# Ports.net
KiCad netlist of a schematic drawn in Altium Designer
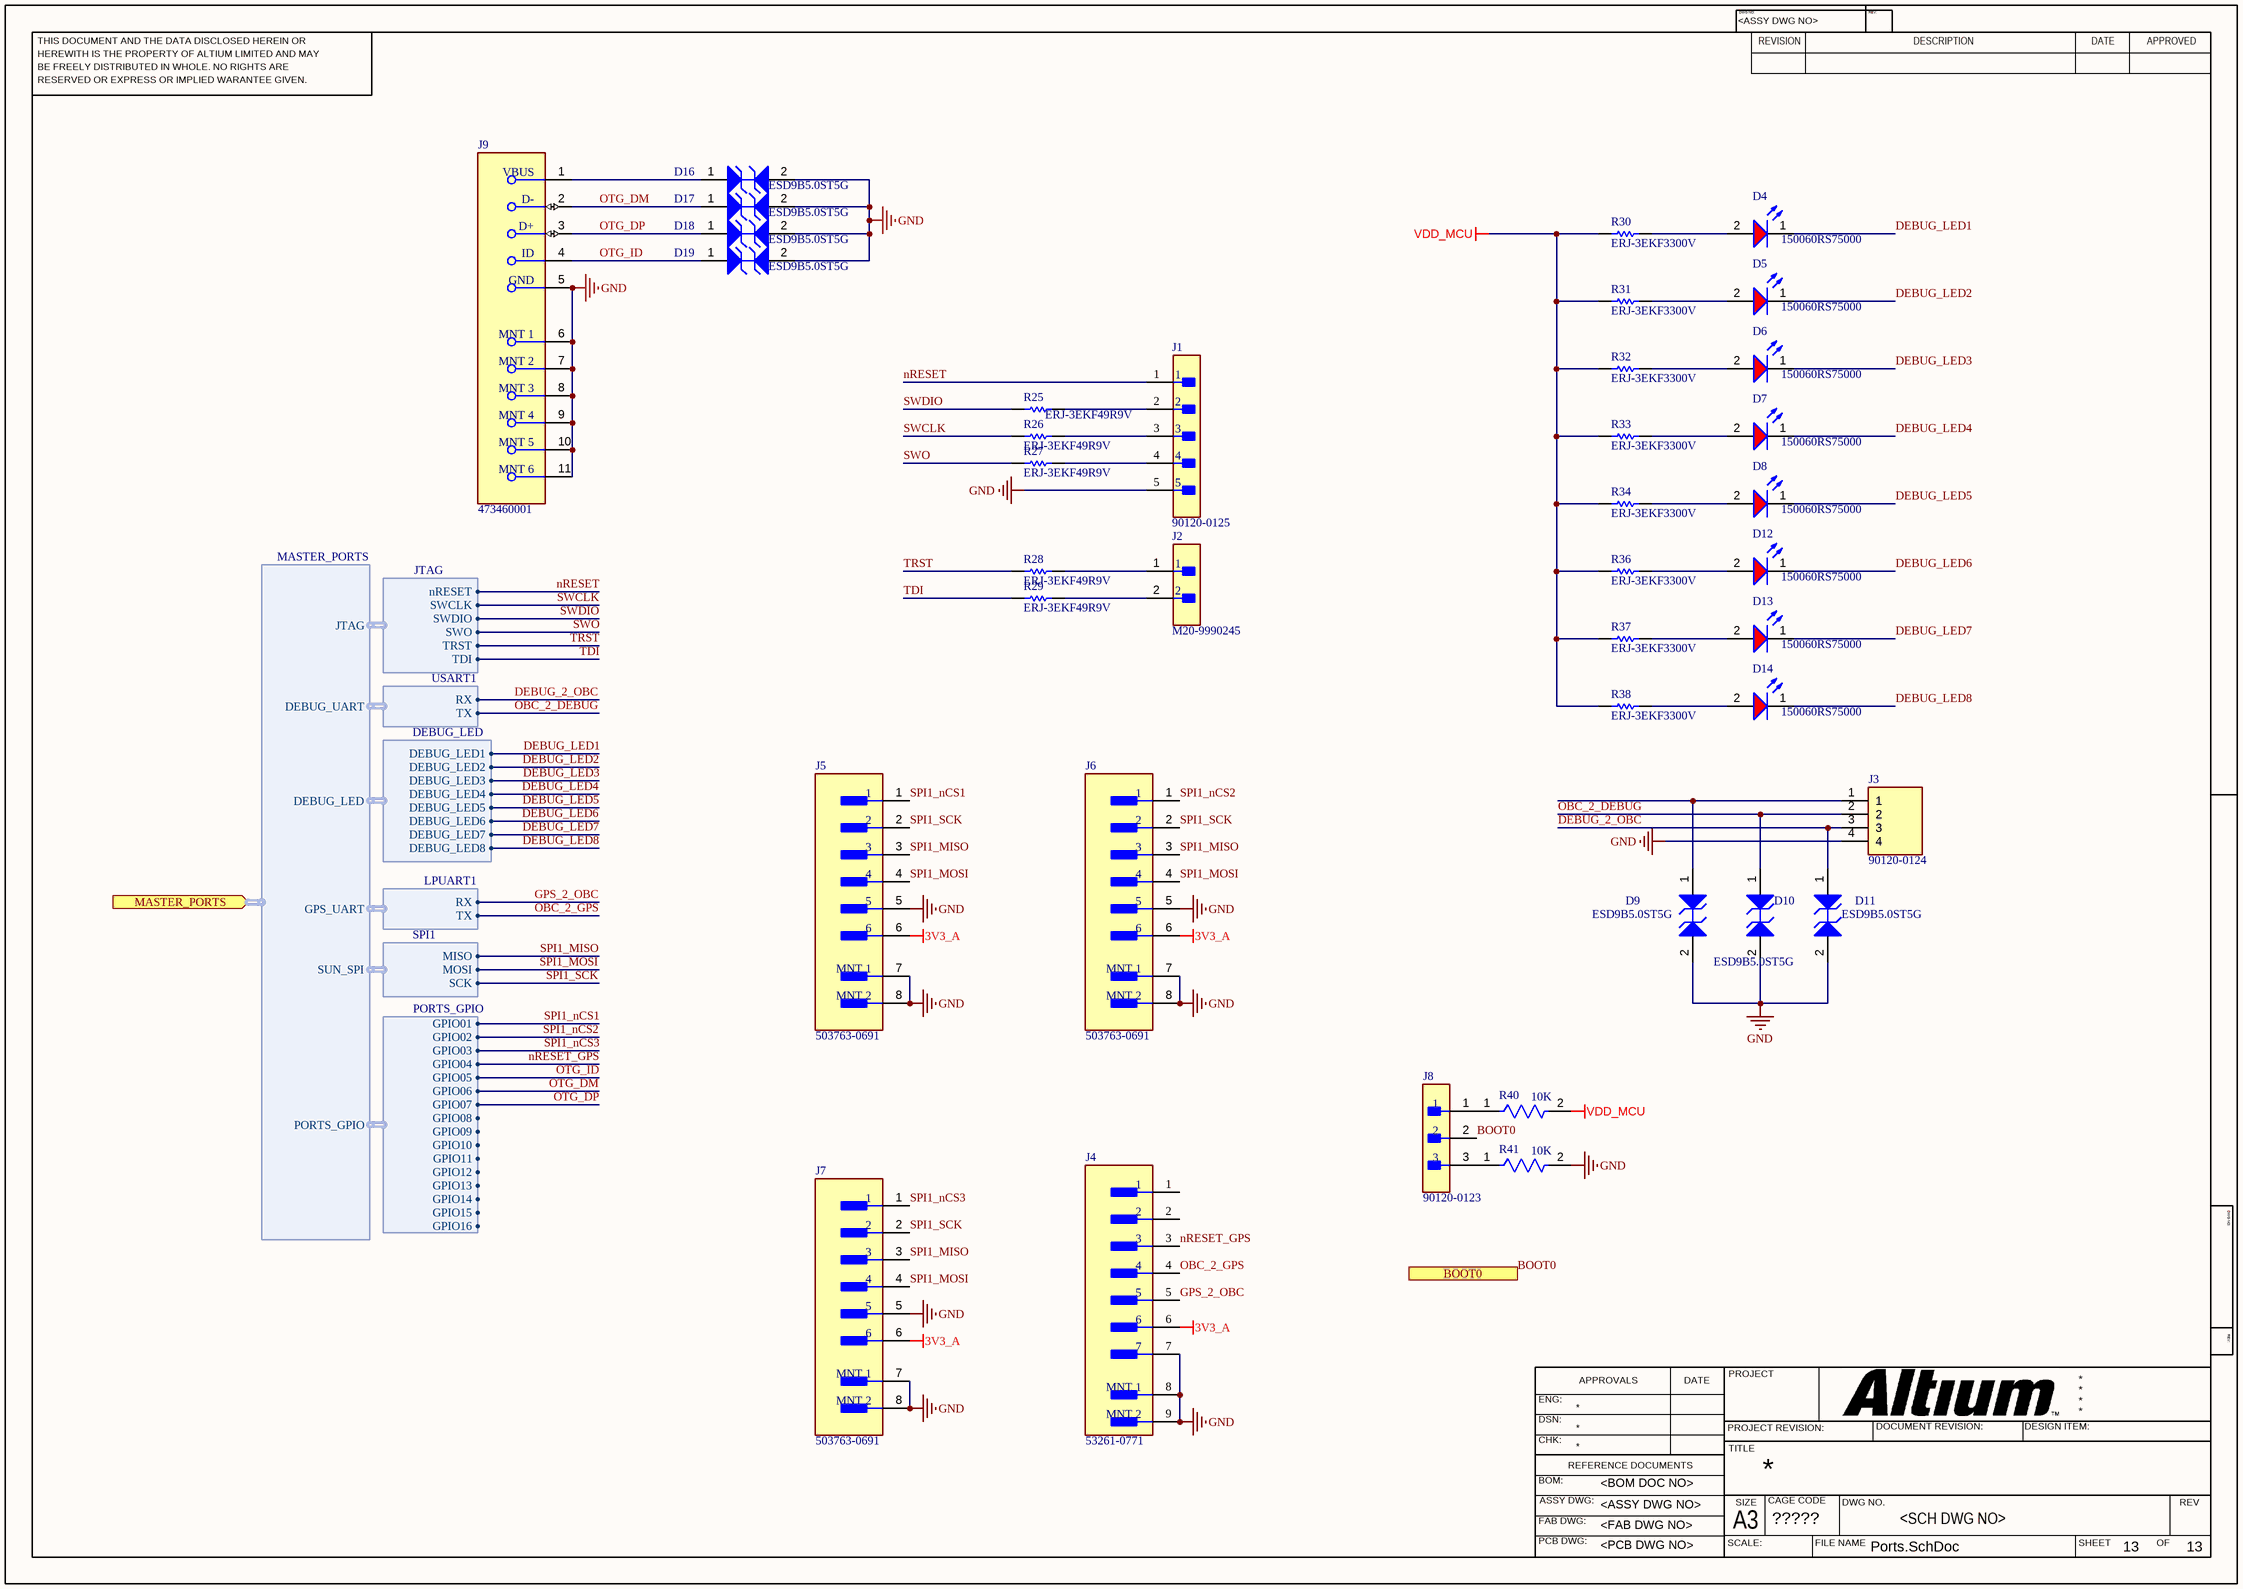
[diagram p0: Ports.SchDoc]

(export (version "E")
  (design (tool "Eeschema 10.0.6"))
  (components
    (comp (ref "D4")
      (value "150060RS75000")
      (footprint "WL-SMCW_0603_150060xx75000")
      (description "LED Low-Power Uni-Color Red 630nm 2V 2-Pin Chip 0603(1608Metric) T/R")
      (libsource (lib "Altium Content Vault") (part "LED_Red_2A-1K"))
    )
    (comp (ref "D5")
      (value "150060RS75000")
      (footprint "WL-SMCW_0603_150060xx75000")
      (description "LED Low-Power Uni-Color Red 630nm 2V 2-Pin Chip 0603(1608Metric) T/R")
      (libsource (lib "Altium Content Vault") (part "LED_Red_2A-1K"))
    )
    (comp (ref "D6")
      (value "150060RS75000")
      (footprint "WL-SMCW_0603_150060xx75000")
      (description "LED Low-Power Uni-Color Red 630nm 2V 2-Pin Chip 0603(1608Metric) T/R")
      (libsource (lib "Altium Content Vault") (part "LED_Red_2A-1K"))
    )
    (comp (ref "D7")
      (value "150060RS75000")
      (footprint "WL-SMCW_0603_150060xx75000")
      (description "LED Low-Power Uni-Color Red 630nm 2V 2-Pin Chip 0603(1608Metric) T/R")
      (libsource (lib "Altium Content Vault") (part "LED_Red_2A-1K"))
    )
    (comp (ref "D8")
      (value "150060RS75000")
      (footprint "WL-SMCW_0603_150060xx75000")
      (description "LED Low-Power Uni-Color Red 630nm 2V 2-Pin Chip 0603(1608Metric) T/R")
      (libsource (lib "Altium Content Vault") (part "LED_Red_2A-1K"))
    )
    (comp (ref "D9")
      (value "ESD9B5.0ST5G")
      (footprint "ONSC-SOD-923-2-514AB-01_V")
      (fields (field (name "MANUFACTURER") "On Semiconductor"))
      (libsource (lib "Altium Content Vault") (part "ONSC-A1A2-2"))
    )
    (comp (ref "D10")
      (value "ESD9B5.0ST5G")
      (footprint "ONSC-SOD-923-2-514AB-01_V")
      (fields (field (name "MANUFACTURER") "On Semiconductor"))
      (libsource (lib "Altium Content Vault") (part "ONSC-A1A2-2"))
    )
    (comp (ref "D11")
      (value "ESD9B5.0ST5G")
      (footprint "ONSC-SOD-923-2-514AB-01_V")
      (fields (field (name "MANUFACTURER") "On Semiconductor"))
      (libsource (lib "Altium Content Vault") (part "ONSC-A1A2-2"))
    )
    (comp (ref "D12")
      (value "150060RS75000")
      (footprint "WL-SMCW_0603_150060xx75000")
      (description "LED Low-Power Uni-Color Red 630nm 2V 2-Pin Chip 0603(1608Metric) T/R")
      (libsource (lib "Altium Content Vault") (part "LED_Red_2A-1K"))
    )
    (comp (ref "D13")
      (value "150060RS75000")
      (footprint "WL-SMCW_0603_150060xx75000")
      (description "LED Low-Power Uni-Color Red 630nm 2V 2-Pin Chip 0603(1608Metric) T/R")
      (libsource (lib "Altium Content Vault") (part "LED_Red_2A-1K"))
    )
    (comp (ref "D14")
      (value "150060RS75000")
      (footprint "WL-SMCW_0603_150060xx75000")
      (description "LED Low-Power Uni-Color Red 630nm 2V 2-Pin Chip 0603(1608Metric) T/R")
      (libsource (lib "Altium Content Vault") (part "LED_Red_2A-1K"))
    )
    (comp (ref "D16")
      (value "ESD9B5.0ST5G")
      (footprint "ONSC-SOD-923-2-514AB-01_V")
      (fields (field (name "MANUFACTURER") "On Semiconductor"))
      (libsource (lib "Altium Content Vault") (part "ONSC-A1A2-2"))
    )
    (comp (ref "D17")
      (value "ESD9B5.0ST5G")
      (footprint "ONSC-SOD-923-2-514AB-01_V")
      (fields (field (name "MANUFACTURER") "On Semiconductor"))
      (libsource (lib "Altium Content Vault") (part "ONSC-A1A2-2"))
    )
    (comp (ref "D18")
      (value "ESD9B5.0ST5G")
      (footprint "ONSC-SOD-923-2-514AB-01_V")
      (fields (field (name "MANUFACTURER") "On Semiconductor"))
      (libsource (lib "Altium Content Vault") (part "ONSC-A1A2-2"))
    )
    (comp (ref "D19")
      (value "ESD9B5.0ST5G")
      (footprint "ONSC-SOD-923-2-514AB-01_V")
      (fields (field (name "MANUFACTURER") "On Semiconductor"))
      (libsource (lib "Altium Content Vault") (part "ONSC-A1A2-2"))
    )
    (comp (ref "J1")
      (value "90120-0125")
      (footprint "FP-90120-0125-MFG")
      (description "90120-0125 2.54mm Pitch C-Grid III Header, Single Row, Vertical, 5 Circuits, Tin (Sn) Plating")
      (libsource (lib "Altium Content Vault") (part "bf93c07fd2649a848d0ec8585582aab"))
    )
    (comp (ref "J2")
      (value "M20-9990245")
      (footprint "FP-M20-9990245-MFG")
      (description "CONN HEADER VERT 2POS 2.54MM")
      (fields (field (name "VOLTAGE") "50V"))
      (libsource (lib "Altium Content Vault") (part "3bc925449376181038e59eaffc5286c"))
    )
    (comp (ref "J3")
      (value "90120-0124")
      (footprint "SamacSys:HDRV4W65P0X254_1X4_1016X254X945P")
      (description "Connector")
      (fields (field (name "MOUSER PART NUMBER") "538-90120-0124"))
      (libsource (lib "*") (part "90120-0124"))
    )
    (comp (ref "J4")
      (value "53261-0771")
      (footprint "FP-53261-0771-MFG")
      (description "CONN HEADER SMD R/A 7POS 1.25MM")
      (libsource (lib "Altium Content Vault") (part "bf8db8d8d9f0c3af2da8de9d3b974a9"))
    )
    (comp (ref "J5")
      (value "503763-0691")
      (footprint "FP-503763-0691-MFG")
      (description "CONN HEADER SMD R/A 6POS 1MM")
      (libsource (lib "Altium Content Vault") (part "ed24c53d9ba001d1a2a686240a95171"))
    )
    (comp (ref "J6")
      (value "503763-0691")
      (footprint "FP-503763-0691-MFG")
      (description "CONN HEADER SMD R/A 6POS 1MM")
      (libsource (lib "Altium Content Vault") (part "ed24c53d9ba001d1a2a686240a95171"))
    )
    (comp (ref "J7")
      (value "503763-0691")
      (footprint "FP-503763-0691-MFG")
      (description "CONN HEADER SMD R/A 6POS 1MM")
      (libsource (lib "Altium Content Vault") (part "ed24c53d9ba001d1a2a686240a95171"))
    )
    (comp (ref "J8")
      (value "90120-0123")
      (footprint "FP-90120-0123-MFG")
      (description "CONN HEADER VERT 3POS 2.54MM")
      (libsource (lib "Altium Content Vault") (part "0d3f023dd272f625e17a2be33dea85f"))
    )
    (comp (ref "J9")
      (value "473460001")
      (footprint "FP-473460001-MFG")
      (description "CONN RCPT USB2.0 MICRO B SMD R/A")
      (fields
        (field (name "OCTOPART") "https://octopart.com/47346-0001-molex-7164928")
        (field (name "MANUFACTURER") "Molex")
      )
      (libsource (lib "Altium Content Vault") (part "53ae1f1d9b557310b43ca686e5bb76a"))
    )
    (comp (ref "R25")
      (value "ERJ-3EKF49R9V")
      (footprint "RESC1608X55X30ML15T15")
      (fields (field (name "MANUFACTURER") "Panasonic"))
      (libsource (lib "Altium Content Vault") (part "RES"))
    )
    (comp (ref "R26")
      (value "ERJ-3EKF49R9V")
      (footprint "RESC1608X55X30ML15T15")
      (fields (field (name "MANUFACTURER") "Panasonic"))
      (libsource (lib "Altium Content Vault") (part "RES"))
    )
    (comp (ref "R27")
      (value "ERJ-3EKF49R9V")
      (footprint "RESC1608X55X30ML15T15")
      (fields (field (name "MANUFACTURER") "Panasonic"))
      (libsource (lib "Altium Content Vault") (part "RES"))
    )
    (comp (ref "R28")
      (value "ERJ-3EKF49R9V")
      (footprint "RESC1608X55X30ML15T15")
      (fields (field (name "MANUFACTURER") "Panasonic"))
      (libsource (lib "Altium Content Vault") (part "RES"))
    )
    (comp (ref "R29")
      (value "ERJ-3EKF49R9V")
      (footprint "RESC1608X55X30ML15T15")
      (fields (field (name "MANUFACTURER") "Panasonic"))
      (libsource (lib "Altium Content Vault") (part "RES"))
    )
    (comp (ref "R30")
      (value "ERJ-3EKF3300V")
      (footprint "RESC1608X55X30LL15T15")
      (description "Chip Resistor, 330 Ohm, +/- 1%, 0.1 W, -55 to 155 degC, 0603 (1608 Metric), RoHS, Tape and Reel")
      (libsource (lib "Altium Content Vault") (part "RES-2"))
    )
    (comp (ref "R31")
      (value "ERJ-3EKF3300V")
      (footprint "RESC1608X55X30LL15T15")
      (description "Chip Resistor, 330 Ohm, +/- 1%, 0.1 W, -55 to 155 degC, 0603 (1608 Metric), RoHS, Tape and Reel")
      (libsource (lib "Altium Content Vault") (part "RES-2"))
    )
    (comp (ref "R32")
      (value "ERJ-3EKF3300V")
      (footprint "RESC1608X55X30LL15T15")
      (description "Chip Resistor, 330 Ohm, +/- 1%, 0.1 W, -55 to 155 degC, 0603 (1608 Metric), RoHS, Tape and Reel")
      (libsource (lib "Altium Content Vault") (part "RES-2"))
    )
    (comp (ref "R33")
      (value "ERJ-3EKF3300V")
      (footprint "RESC1608X55X30LL15T15")
      (description "Chip Resistor, 330 Ohm, +/- 1%, 0.1 W, -55 to 155 degC, 0603 (1608 Metric), RoHS, Tape and Reel")
      (libsource (lib "Altium Content Vault") (part "RES-2"))
    )
    (comp (ref "R34")
      (value "ERJ-3EKF3300V")
      (footprint "RESC1608X55X30LL15T15")
      (description "Chip Resistor, 330 Ohm, +/- 1%, 0.1 W, -55 to 155 degC, 0603 (1608 Metric), RoHS, Tape and Reel")
      (libsource (lib "Altium Content Vault") (part "RES-2"))
    )
    (comp (ref "R36")
      (value "ERJ-3EKF3300V")
      (footprint "RESC1608X55X30LL15T15")
      (description "Chip Resistor, 330 Ohm, +/- 1%, 0.1 W, -55 to 155 degC, 0603 (1608 Metric), RoHS, Tape and Reel")
      (libsource (lib "Altium Content Vault") (part "RES-2"))
    )
    (comp (ref "R37")
      (value "ERJ-3EKF3300V")
      (footprint "RESC1608X55X30LL15T15")
      (description "Chip Resistor, 330 Ohm, +/- 1%, 0.1 W, -55 to 155 degC, 0603 (1608 Metric), RoHS, Tape and Reel")
      (libsource (lib "Altium Content Vault") (part "RES-2"))
    )
    (comp (ref "R38")
      (value "ERJ-3EKF3300V")
      (footprint "RESC1608X55X30LL15T15")
      (description "Chip Resistor, 330 Ohm, +/- 1%, 0.1 W, -55 to 155 degC, 0603 (1608 Metric), RoHS, Tape and Reel")
      (libsource (lib "Altium Content Vault") (part "RES-2"))
    )
    (comp (ref "R40")
      (value "10K")
      (footprint "FP-RK73B1J-MFG")
      (description "RES 10K OHM 5% 1/10W 0603")
      (fields (field (name "TOLERANCE") "5%"))
      (libsource (lib "Altium Content Vault") (part "1029c3af85768c4190bb7ad29bc67b5"))
    )
    (comp (ref "R41")
      (value "10K")
      (footprint "FP-RK73B1J-MFG")
      (description "RES 10K OHM 5% 1/10W 0603")
      (fields (field (name "TOLERANCE") "5%"))
      (libsource (lib "Altium Content Vault") (part "1029c3af85768c4190bb7ad29bc67b5"))
    )
  )
  (nets
    (net (code "8") (name "/BOOT0") (class "Default")
      (node (ref "J8") (pin "2") (pinfunction "2_2") (pintype "passive"))
    )
    (net (code "9") (name "/DEBUG_2_OBC") (class "Default")
      (node (ref "D11") (pin "1") (pinfunction "A1_1") (pintype "passive"))
      (node (ref "J3") (pin "3") (pinfunction "3_3") (pintype "passive"))
    )
    (net (code "10") (name "/DEBUG_LED1") (class "Default")
      (node (ref "D4") (pin "1") (pinfunction "K_1") (pintype "passive"))
    )
    (net (code "11") (name "/DEBUG_LED2") (class "Default")
      (node (ref "D5") (pin "1") (pinfunction "K_1") (pintype "passive"))
    )
    (net (code "12") (name "/DEBUG_LED3") (class "Default")
      (node (ref "D6") (pin "1") (pinfunction "K_1") (pintype "passive"))
    )
    (net (code "13") (name "/DEBUG_LED4") (class "Default")
      (node (ref "D7") (pin "1") (pinfunction "K_1") (pintype "passive"))
    )
    (net (code "14") (name "/DEBUG_LED5") (class "Default")
      (node (ref "D8") (pin "1") (pinfunction "K_1") (pintype "passive"))
    )
    (net (code "15") (name "/DEBUG_LED6") (class "Default")
      (node (ref "D12") (pin "1") (pinfunction "K_1") (pintype "passive"))
    )
    (net (code "16") (name "/DEBUG_LED7") (class "Default")
      (node (ref "D13") (pin "1") (pinfunction "K_1") (pintype "passive"))
    )
    (net (code "17") (name "/DEBUG_LED8") (class "Default")
      (node (ref "D14") (pin "1") (pinfunction "K_1") (pintype "passive"))
    )
    (net (code "18") (name "/GPS_2_OBC") (class "Default")
      (node (ref "J4") (pin "5") (pinfunction "5_5") (pintype "passive"))
    )
    (net (code "20") (name "/OBC_2_DEBUG") (class "Default")
      (node (ref "D10") (pin "1") (pinfunction "A1_1") (pintype "passive"))
      (node (ref "J3") (pin "2") (pinfunction "2_2") (pintype "passive"))
    )
    (net (code "21") (name "/OBC_2_GPS") (class "Default")
      (node (ref "J4") (pin "4") (pinfunction "4_4") (pintype "passive"))
    )
    (net (code "22") (name "/OTG_DM") (class "Default")
      (node (ref "D17") (pin "1") (pinfunction "A1_1") (pintype "passive"))
      (node (ref "J9") (pin "2") (pinfunction "D-_2") (pintype "bidirectional"))
    )
    (net (code "23") (name "/OTG_DP") (class "Default")
      (node (ref "D18") (pin "1") (pinfunction "A1_1") (pintype "passive"))
      (node (ref "J9") (pin "3") (pinfunction "D+_3") (pintype "bidirectional"))
    )
    (net (code "24") (name "/OTG_ID") (class "Default")
      (node (ref "D19") (pin "1") (pinfunction "A1_1") (pintype "passive"))
      (node (ref "J9") (pin "4") (pinfunction "ID_4") (pintype "passive"))
    )
    (net (code "25") (name "/SPI1_MISO") (class "Default")
      (node (ref "J5") (pin "3") (pinfunction "3_3") (pintype "passive"))
      (node (ref "J6") (pin "3") (pinfunction "3_3") (pintype "passive"))
      (node (ref "J7") (pin "3") (pinfunction "3_3") (pintype "passive"))
    )
    (net (code "26") (name "/SPI1_MOSI") (class "Default")
      (node (ref "J5") (pin "4") (pinfunction "4_4") (pintype "passive"))
      (node (ref "J6") (pin "4") (pinfunction "4_4") (pintype "passive"))
      (node (ref "J7") (pin "4") (pinfunction "4_4") (pintype "passive"))
    )
    (net (code "27") (name "/SPI1_SCK") (class "Default")
      (node (ref "J5") (pin "2") (pinfunction "2_2") (pintype "passive"))
      (node (ref "J6") (pin "2") (pinfunction "2_2") (pintype "passive"))
      (node (ref "J7") (pin "2") (pinfunction "2_2") (pintype "passive"))
    )
    (net (code "28") (name "/SPI1_nCS1") (class "Default")
      (node (ref "J5") (pin "1") (pinfunction "1_1") (pintype "passive"))
    )
    (net (code "29") (name "/SPI1_nCS2") (class "Default")
      (node (ref "J6") (pin "1") (pinfunction "1_1") (pintype "passive"))
    )
    (net (code "30") (name "/SPI1_nCS3") (class "Default")
      (node (ref "J7") (pin "1") (pinfunction "1_1") (pintype "passive"))
    )
    (net (code "31") (name "/SWCLK") (class "Default")
      (node (ref "R26") (pin "1") (pinfunction "1_1") (pintype "passive"))
    )
    (net (code "32") (name "/SWDIO") (class "Default")
      (node (ref "R25") (pin "1") (pinfunction "1_1") (pintype "passive"))
    )
    (net (code "33") (name "/SWO") (class "Default")
      (node (ref "R27") (pin "1") (pinfunction "1_1") (pintype "passive"))
    )
    (net (code "34") (name "/TDI") (class "Default")
      (node (ref "R29") (pin "1") (pinfunction "1_1") (pintype "passive"))
    )
    (net (code "35") (name "/TRST") (class "Default")
      (node (ref "R28") (pin "1") (pinfunction "1_1") (pintype "passive"))
    )
    (net (code "36") (name "/nRESET") (class "Default")
      (node (ref "J1") (pin "1") (pinfunction "1_1") (pintype "passive"))
    )
    (net (code "37") (name "/nRESET_GPS") (class "Default")
      (node (ref "J4") (pin "3") (pinfunction "3_3") (pintype "passive"))
    )
    (net (code "44") (name "3V3_A") (class "Default")
      (node (ref "J4") (pin "6") (pinfunction "6_6") (pintype "passive"))
      (node (ref "J5") (pin "6") (pinfunction "6_6") (pintype "passive"))
      (node (ref "J6") (pin "6") (pinfunction "6_6") (pintype "passive"))
      (node (ref "J7") (pin "6") (pinfunction "6_6") (pintype "passive"))
    )
    (net (code "45") (name "GND") (class "Default")
      (node (ref "D10") (pin "2") (pinfunction "A2_2") (pintype "passive"))
      (node (ref "D11") (pin "2") (pinfunction "A2_2") (pintype "passive"))
      (node (ref "D16") (pin "2") (pinfunction "A2_2") (pintype "passive"))
      (node (ref "D17") (pin "2") (pinfunction "A2_2") (pintype "passive"))
      (node (ref "D18") (pin "2") (pinfunction "A2_2") (pintype "passive"))
      (node (ref "D19") (pin "2") (pinfunction "A2_2") (pintype "passive"))
      (node (ref "D9") (pin "2") (pinfunction "A2_2") (pintype "passive"))
      (node (ref "J1") (pin "5") (pinfunction "5_5") (pintype "passive"))
      (node (ref "J3") (pin "4") (pinfunction "4_4") (pintype "passive"))
      (node (ref "J4") (pin "7") (pinfunction "7_7") (pintype "passive"))
      (node (ref "J4") (pin "8") (pinfunction "MNT_1_8") (pintype "passive"))
      (node (ref "J4") (pin "9") (pinfunction "MNT_2_9") (pintype "passive"))
      (node (ref "J5") (pin "5") (pinfunction "5_5") (pintype "passive"))
      (node (ref "J5") (pin "7") (pinfunction "MNT_1_7") (pintype "passive"))
      (node (ref "J5") (pin "8") (pinfunction "MNT_2_8") (pintype "passive"))
      (node (ref "J6") (pin "5") (pinfunction "5_5") (pintype "passive"))
      (node (ref "J6") (pin "7") (pinfunction "MNT_1_7") (pintype "passive"))
      (node (ref "J6") (pin "8") (pinfunction "MNT_2_8") (pintype "passive"))
      (node (ref "J7") (pin "5") (pinfunction "5_5") (pintype "passive"))
      (node (ref "J7") (pin "7") (pinfunction "MNT_1_7") (pintype "passive"))
      (node (ref "J7") (pin "8") (pinfunction "MNT_2_8") (pintype "passive"))
      (node (ref "J9") (pin "10") (pinfunction "MNT_5_10") (pintype "passive"))
      (node (ref "J9") (pin "11") (pinfunction "MNT_6_11") (pintype "passive"))
      (node (ref "J9") (pin "5") (pinfunction "GND_5") (pintype "power_in"))
      (node (ref "J9") (pin "6") (pinfunction "MNT_1_6") (pintype "passive"))
      (node (ref "J9") (pin "7") (pinfunction "MNT_2_7") (pintype "passive"))
      (node (ref "J9") (pin "8") (pinfunction "MNT_3_8") (pintype "passive"))
      (node (ref "J9") (pin "9") (pinfunction "MNT_4_9") (pintype "passive"))
      (node (ref "R41") (pin "2") (pinfunction "2_2") (pintype "passive"))
    )
    (net (code "46") (name "Net-(D4-A)") (class "Default")
      (node (ref "D4") (pin "2") (pinfunction "A_2") (pintype "passive"))
      (node (ref "R30") (pin "2") (pinfunction "2_2") (pintype "passive"))
    )
    (net (code "47") (name "Net-(D5-A)") (class "Default")
      (node (ref "D5") (pin "2") (pinfunction "A_2") (pintype "passive"))
      (node (ref "R31") (pin "2") (pinfunction "2_2") (pintype "passive"))
    )
    (net (code "48") (name "Net-(D6-A)") (class "Default")
      (node (ref "D6") (pin "2") (pinfunction "A_2") (pintype "passive"))
      (node (ref "R32") (pin "2") (pinfunction "2_2") (pintype "passive"))
    )
    (net (code "49") (name "Net-(D7-A)") (class "Default")
      (node (ref "D7") (pin "2") (pinfunction "A_2") (pintype "passive"))
      (node (ref "R33") (pin "2") (pinfunction "2_2") (pintype "passive"))
    )
    (net (code "50") (name "Net-(D8-A)") (class "Default")
      (node (ref "D8") (pin "2") (pinfunction "A_2") (pintype "passive"))
      (node (ref "R34") (pin "2") (pinfunction "2_2") (pintype "passive"))
    )
    (net (code "51") (name "Net-(D9-A1)") (class "Default")
      (node (ref "D9") (pin "1") (pinfunction "A1_1") (pintype "passive"))
      (node (ref "J3") (pin "1") (pinfunction "1_1") (pintype "passive"))
    )
    (net (code "52") (name "Net-(D12-A)") (class "Default")
      (node (ref "D12") (pin "2") (pinfunction "A_2") (pintype "passive"))
      (node (ref "R36") (pin "2") (pinfunction "2_2") (pintype "passive"))
    )
    (net (code "53") (name "Net-(D13-A)") (class "Default")
      (node (ref "D13") (pin "2") (pinfunction "A_2") (pintype "passive"))
      (node (ref "R37") (pin "2") (pinfunction "2_2") (pintype "passive"))
    )
    (net (code "54") (name "Net-(D14-A)") (class "Default")
      (node (ref "D14") (pin "2") (pinfunction "A_2") (pintype "passive"))
      (node (ref "R38") (pin "2") (pinfunction "2_2") (pintype "passive"))
    )
    (net (code "55") (name "Net-(D16-A1)") (class "Default")
      (node (ref "D16") (pin "1") (pinfunction "A1_1") (pintype "passive"))
      (node (ref "J9") (pin "1") (pinfunction "VBUS_1") (pintype "power_in"))
    )
    (net (code "56") (name "Net-(J1-Pad2)") (class "Default")
      (node (ref "J1") (pin "2") (pinfunction "2_2") (pintype "passive"))
      (node (ref "R25") (pin "2") (pinfunction "2_2") (pintype "passive"))
    )
    (net (code "57") (name "Net-(J1-Pad3)") (class "Default")
      (node (ref "J1") (pin "3") (pinfunction "3_3") (pintype "passive"))
      (node (ref "R26") (pin "2") (pinfunction "2_2") (pintype "passive"))
    )
    (net (code "58") (name "Net-(J1-Pad4)") (class "Default")
      (node (ref "J1") (pin "4") (pinfunction "4_4") (pintype "passive"))
      (node (ref "R27") (pin "2") (pinfunction "2_2") (pintype "passive"))
    )
    (net (code "59") (name "Net-(J2-Pad1)") (class "Default")
      (node (ref "J2") (pin "1") (pinfunction "1_1") (pintype "passive"))
      (node (ref "R28") (pin "2") (pinfunction "2_2") (pintype "passive"))
    )
    (net (code "60") (name "Net-(J2-Pad2)") (class "Default")
      (node (ref "J2") (pin "2") (pinfunction "2_2") (pintype "passive"))
      (node (ref "R29") (pin "2") (pinfunction "2_2") (pintype "passive"))
    )
    (net (code "61") (name "Net-(J8-Pad1)") (class "Default")
      (node (ref "J8") (pin "1") (pinfunction "1_1") (pintype "passive"))
      (node (ref "R40") (pin "1") (pinfunction "1_1") (pintype "passive"))
    )
    (net (code "62") (name "Net-(J8-Pad3)") (class "Default")
      (node (ref "J8") (pin "3") (pinfunction "3_3") (pintype "passive"))
      (node (ref "R41") (pin "1") (pinfunction "1_1") (pintype "passive"))
    )
    (net (code "63") (name "VDD_MCU") (class "Default")
      (node (ref "R30") (pin "1") (pinfunction "1_1") (pintype "passive"))
      (node (ref "R31") (pin "1") (pinfunction "1_1") (pintype "passive"))
      (node (ref "R32") (pin "1") (pinfunction "1_1") (pintype "passive"))
      (node (ref "R33") (pin "1") (pinfunction "1_1") (pintype "passive"))
      (node (ref "R34") (pin "1") (pinfunction "1_1") (pintype "passive"))
      (node (ref "R36") (pin "1") (pinfunction "1_1") (pintype "passive"))
      (node (ref "R37") (pin "1") (pinfunction "1_1") (pintype "passive"))
      (node (ref "R38") (pin "1") (pinfunction "1_1") (pintype "passive"))
      (node (ref "R40") (pin "2") (pinfunction "2_2") (pintype "passive"))
    )
    (net (code "64") (name "unconnected-(J4-Pad1)") (class "Default")
      (node (ref "J4") (pin "1") (pinfunction "1_1") (pintype "passive"))
    )
    (net (code "65") (name "unconnected-(J4-Pad2)") (class "Default")
      (node (ref "J4") (pin "2") (pinfunction "2_2") (pintype "passive"))
    )
  )
)
